# UVB_LED_Controller.net
KiCad netlist of a schematic drawn in Altium Designer
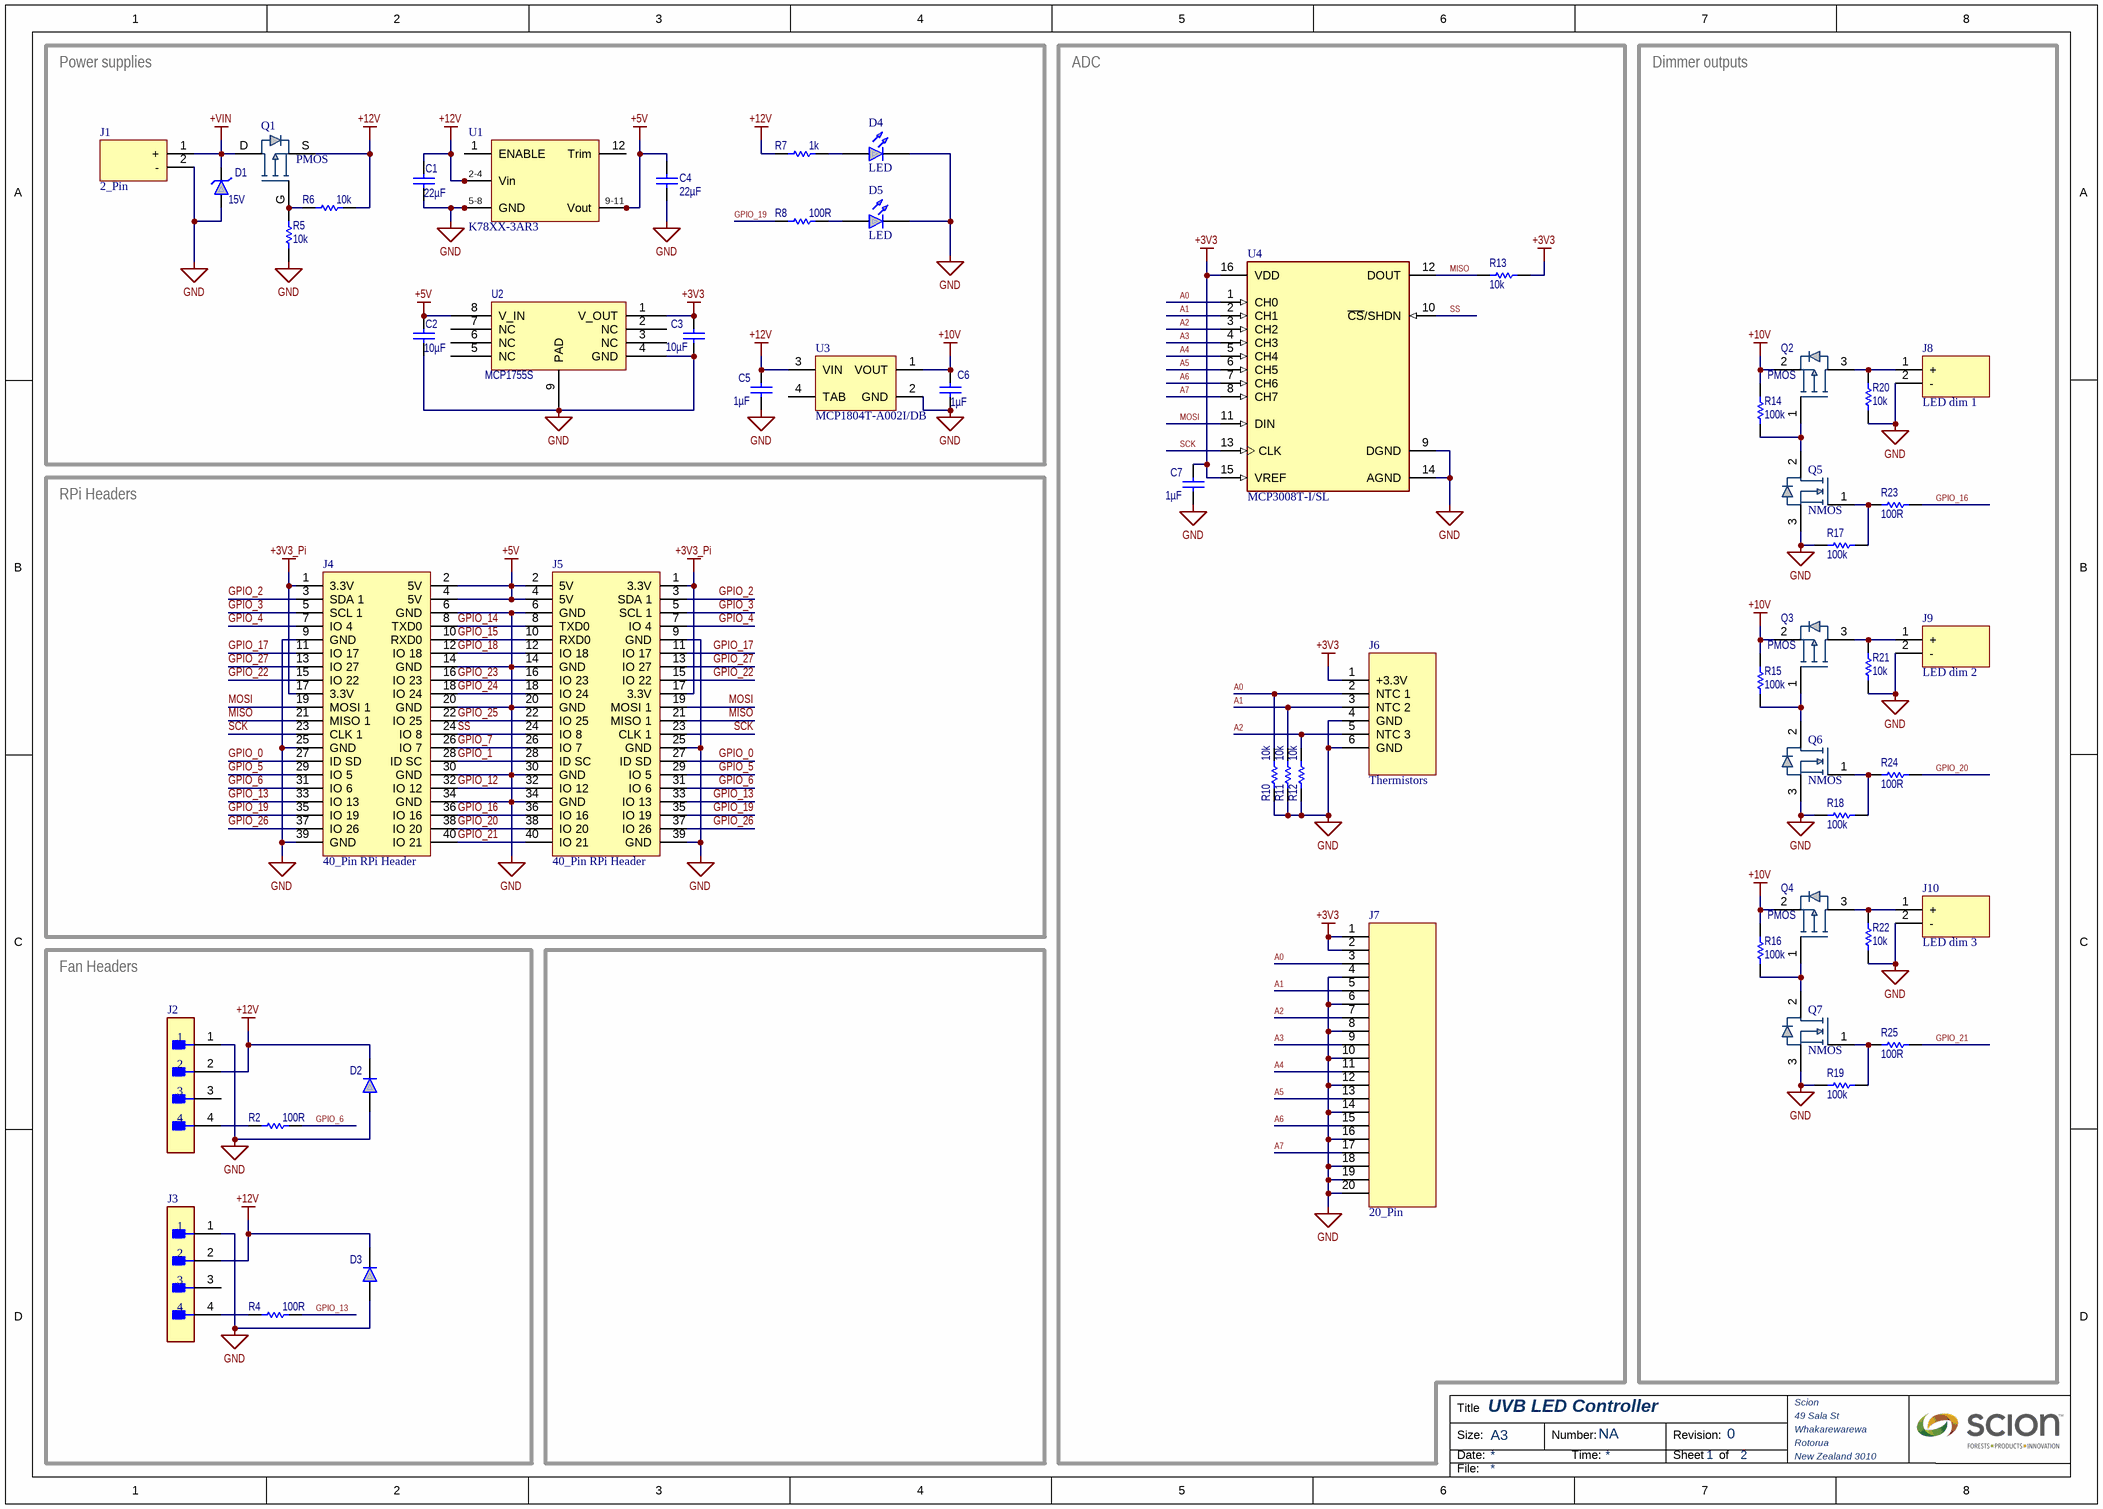
[diagram p0: UVB LED Controller.SchDoc]

(export (version "E")
  (design (tool "Eeschema 10.0.6"))
  (components
    (comp (ref "C1")
      (value "22µF")
      (footprint "1206_CAP")
      (description "SMD Capacitor")
      (fields (field (name "Comment") "Capacitor"))
      (libsource (lib "Scion Research") (part "CMP-019-00005-2"))
    )
    (comp (ref "C2")
      (value "10µF")
      (footprint "0603_CAP")
      (description "SMD Capacitor")
      (fields (field (name "Comment") "Capacitor"))
      (libsource (lib "Scion Research") (part "CMP-019-00005-2"))
    )
    (comp (ref "C3")
      (value "10µF")
      (footprint "0603_CAP")
      (description "SMD Capacitor")
      (fields (field (name "Comment") "Capacitor"))
      (libsource (lib "Scion Research") (part "CMP-019-00005-2"))
    )
    (comp (ref "C4")
      (value "22µF")
      (footprint "1206_CAP")
      (description "SMD Capacitor")
      (fields (field (name "Comment") "Capacitor"))
      (libsource (lib "Scion Research") (part "CMP-019-00005-2"))
    )
    (comp (ref "C5")
      (value "1µF")
      (footprint "0603_CAP")
      (description "SMD Capacitor")
      (fields (field (name "Comment") "Capacitor"))
      (libsource (lib "Scion Research") (part "CMP-019-00005-2"))
    )
    (comp (ref "C6")
      (value "1µF")
      (footprint "0603_CAP")
      (description "SMD Capacitor")
      (fields (field (name "Comment") "Capacitor"))
      (libsource (lib "Scion Research") (part "CMP-019-00005-2"))
    )
    (comp (ref "C7")
      (value "1µF")
      (footprint "0603_CAP")
      (description "SMD Capacitor")
      (fields (field (name "Comment") "Capacitor"))
      (libsource (lib "Scion Research") (part "CMP-019-00005-2"))
    )
    (comp (ref "D1")
      (value "Transil")
      (footprint "SMBJ")
      (description "Transient Voltage Suppressor")
      (fields (field (name "RATED VOLTAGE") "15V"))
      (libsource (lib "Scion Research") (part "CMP-004-0042-1"))
    )
    (comp (ref "D2")
      (value "Diode")
      (footprint "SOD-123")
      (description "SMD Diode")
      (libsource (lib "Scion Research") (part "Diode"))
    )
    (comp (ref "D3")
      (value "Diode")
      (footprint "SOD-123")
      (description "SMD Diode")
      (libsource (lib "Scion Research") (part "Diode"))
    )
    (comp (ref "D4")
      (value "LED")
      (footprint "KPA-2106S_LED")
      (description "SMD LED")
      (libsource (lib "Scion Research") (part "CMP-004-00032-1"))
    )
    (comp (ref "D5")
      (value "LED")
      (footprint "KPA-2106S_LED")
      (description "SMD LED")
      (libsource (lib "Scion Research") (part "CMP-004-00032-1"))
    )
    (comp (ref "J1")
      (value "2_Pin")
      (footprint "2P 3.81mm Header Plugable")
      (description "2 Pin Connector")
      (libsource (lib "") (part "CMP-002-00074-8_1"))
    )
    (comp (ref "J2")
      (value "22-29-2041")
      (footprint "FP-22-29-2041-MFG")
      (description "CONN HEADER VERT 4POS 2.54MM")
      (libsource (lib "Altium Content Vault") (part "299a8cea1bdcbc3624fe62c390fa72c"))
    )
    (comp (ref "J3")
      (value "22-29-2041")
      (footprint "FP-22-29-2041-MFG")
      (description "CONN HEADER VERT 4POS 2.54MM")
      (libsource (lib "Altium Content Vault") (part "299a8cea1bdcbc3624fe62c390fa72c"))
    )
    (comp (ref "J4")
      (value "40_Pin RPi Header")
      (footprint "40_Pin_0.1in_male_header")
      (description "40 pin header for Raspberry Pi compatible connections")
      (libsource (lib "") (part "40_Pin RPi Header_1"))
    )
    (comp (ref "J5")
      (value "40_Pin RPi Header")
      (footprint "40_Pin_0.1in_female_header")
      (description "40 pin header for Raspberry Pi compatible connections")
      (libsource (lib "Scion Research") (part "40_Pin RPi Header"))
    )
    (comp (ref "J6")
      (value "Thermistors")
      (footprint "6P RA MOLEX Clik-MATE 1.5mm")
      (description "6 Pin Connector")
      (libsource (lib "Scion Research") (part "CMP-002-00081-5"))
    )
    (comp (ref "J7")
      (value "20_Pin")
      (footprint "20P 2.54mm DIP header")
      (description "20 pin connector")
      (libsource (lib "Scion Research") (part "20_Pin-Symbol-1"))
    )
    (comp (ref "J8")
      (value "LED dim 1")
      (footprint "2P 3.81mm Header Plugable")
      (description "2 Pin Connector")
      (libsource (lib "Scion Research") (part "CMP-002-00074-8"))
    )
    (comp (ref "J9")
      (value "LED dim 2")
      (footprint "2P 3.81mm Header Plugable")
      (description "2 Pin Connector")
      (libsource (lib "Scion Research") (part "CMP-002-00074-8"))
    )
    (comp (ref "J10")
      (value "LED dim 3")
      (footprint "2P 3.81mm Header Plugable")
      (description "2 Pin Connector")
      (libsource (lib "Scion Research") (part "CMP-002-00074-8"))
    )
    (comp (ref "Q1")
      (value "PMOS")
      (footprint "PowerDI 5060-8")
      (description "P Channel MOSFET")
      (libsource (lib "Scion Research") (part "CMP-004-0035-2"))
    )
    (comp (ref "Q2")
      (value "PMOS")
      (footprint "SOT-23-PMOS")
      (description "P Channel MOSFET")
      (libsource (lib "Scion Research") (part "CMP-004-0033-1"))
    )
    (comp (ref "Q3")
      (value "PMOS")
      (footprint "SOT-23-PMOS")
      (description "P Channel MOSFET")
      (libsource (lib "Scion Research") (part "CMP-004-0033-1"))
    )
    (comp (ref "Q4")
      (value "PMOS")
      (footprint "SOT-23-PMOS")
      (description "P Channel MOSFET")
      (libsource (lib "Scion Research") (part "CMP-004-0033-1"))
    )
    (comp (ref "Q5")
      (value "NMOS")
      (footprint "SOT-23")
      (description "N Channel MOSFET")
      (libsource (lib "Scion Research") (part "CMP-004-0025-1"))
    )
    (comp (ref "Q6")
      (value "NMOS")
      (footprint "SOT-23")
      (description "N Channel MOSFET")
      (libsource (lib "Scion Research") (part "CMP-004-0025-1"))
    )
    (comp (ref "Q7")
      (value "NMOS")
      (footprint "SOT-23")
      (description "N Channel MOSFET")
      (libsource (lib "Scion Research") (part "CMP-004-0025-1"))
    )
    (comp (ref "R2")
      (value "Resistor")
      (footprint "0603_RES")
      (description "SMD Resistor")
      (fields (field (name "ALTIUM_VALUE") "100R"))
      (libsource (lib "Scion Research") (part "CMP-009-00177-2"))
    )
    (comp (ref "R4")
      (value "Resistor")
      (footprint "0603_RES")
      (description "SMD Resistor")
      (fields (field (name "ALTIUM_VALUE") "100R"))
      (libsource (lib "Scion Research") (part "CMP-009-00177-2"))
    )
    (comp (ref "R5")
      (value "Resistor")
      (footprint "0603_RES")
      (description "SMD Resistor")
      (fields (field (name "ALTIUM_VALUE") "10k"))
      (libsource (lib "Scion Research") (part "CMP-009-00177-2"))
    )
    (comp (ref "R6")
      (value "Resistor")
      (footprint "0603_RES")
      (description "SMD Resistor")
      (fields (field (name "ALTIUM_VALUE") "10k"))
      (libsource (lib "Scion Research") (part "CMP-009-00177-2"))
    )
    (comp (ref "R7")
      (value "Resistor")
      (footprint "0603_RES")
      (description "SMD Resistor")
      (fields (field (name "ALTIUM_VALUE") "1k"))
      (libsource (lib "Scion Research") (part "CMP-009-00177-2"))
    )
    (comp (ref "R8")
      (value "Resistor")
      (footprint "0603_RES")
      (description "SMD Resistor")
      (fields (field (name "ALTIUM_VALUE") "100R"))
      (libsource (lib "Scion Research") (part "CMP-009-00177-2"))
    )
    (comp (ref "R10")
      (value "Resistor")
      (footprint "0603_RES")
      (description "SMD Resistor")
      (fields (field (name "ALTIUM_VALUE") "10k"))
      (libsource (lib "Scion Research") (part "CMP-009-00177-2"))
    )
    (comp (ref "R11")
      (value "Resistor")
      (footprint "0603_RES")
      (description "SMD Resistor")
      (fields (field (name "ALTIUM_VALUE") "10k"))
      (libsource (lib "Scion Research") (part "CMP-009-00177-2"))
    )
    (comp (ref "R12")
      (value "Resistor")
      (footprint "0603_RES")
      (description "SMD Resistor")
      (fields (field (name "ALTIUM_VALUE") "10k"))
      (libsource (lib "Scion Research") (part "CMP-009-00177-2"))
    )
    (comp (ref "R13")
      (value "Resistor")
      (footprint "0603_RES")
      (description "SMD Resistor")
      (fields (field (name "ALTIUM_VALUE") "10k"))
      (libsource (lib "Scion Research") (part "CMP-009-00177-2"))
    )
    (comp (ref "R14")
      (value "Resistor")
      (footprint "0603_RES")
      (description "SMD Resistor")
      (fields (field (name "ALTIUM_VALUE") "100k"))
      (libsource (lib "Scion Research") (part "CMP-009-00177-2"))
    )
    (comp (ref "R15")
      (value "Resistor")
      (footprint "0603_RES")
      (description "SMD Resistor")
      (fields (field (name "ALTIUM_VALUE") "100k"))
      (libsource (lib "Scion Research") (part "CMP-009-00177-2"))
    )
    (comp (ref "R16")
      (value "Resistor")
      (footprint "0603_RES")
      (description "SMD Resistor")
      (fields (field (name "ALTIUM_VALUE") "100k"))
      (libsource (lib "Scion Research") (part "CMP-009-00177-2"))
    )
    (comp (ref "R17")
      (value "Resistor")
      (footprint "0603_RES")
      (description "SMD Resistor")
      (fields (field (name "ALTIUM_VALUE") "100k"))
      (libsource (lib "Scion Research") (part "CMP-009-00177-2"))
    )
    (comp (ref "R18")
      (value "Resistor")
      (footprint "0603_RES")
      (description "SMD Resistor")
      (fields (field (name "ALTIUM_VALUE") "100k"))
      (libsource (lib "Scion Research") (part "CMP-009-00177-2"))
    )
    (comp (ref "R19")
      (value "Resistor")
      (footprint "0603_RES")
      (description "SMD Resistor")
      (fields (field (name "ALTIUM_VALUE") "100k"))
      (libsource (lib "Scion Research") (part "CMP-009-00177-2"))
    )
    (comp (ref "R20")
      (value "Resistor")
      (footprint "0603_RES")
      (description "SMD Resistor")
      (fields (field (name "ALTIUM_VALUE") "10k"))
      (libsource (lib "Scion Research") (part "CMP-009-00177-2"))
    )
    (comp (ref "R21")
      (value "Resistor")
      (footprint "0603_RES")
      (description "SMD Resistor")
      (fields (field (name "ALTIUM_VALUE") "10k"))
      (libsource (lib "Scion Research") (part "CMP-009-00177-2"))
    )
    (comp (ref "R22")
      (value "Resistor")
      (footprint "0603_RES")
      (description "SMD Resistor")
      (fields (field (name "ALTIUM_VALUE") "10k"))
      (libsource (lib "Scion Research") (part "CMP-009-00177-2"))
    )
    (comp (ref "R23")
      (value "Resistor")
      (footprint "0603_RES")
      (description "SMD Resistor")
      (fields (field (name "ALTIUM_VALUE") "100R"))
      (libsource (lib "Scion Research") (part "CMP-009-00177-2"))
    )
    (comp (ref "R24")
      (value "Resistor")
      (footprint "0603_RES")
      (description "SMD Resistor")
      (fields (field (name "ALTIUM_VALUE") "100R"))
      (libsource (lib "Scion Research") (part "CMP-009-00177-2"))
    )
    (comp (ref "R25")
      (value "Resistor")
      (footprint "0603_RES")
      (description "SMD Resistor")
      (fields (field (name "ALTIUM_VALUE") "100R"))
      (libsource (lib "Scion Research") (part "CMP-009-00177-2"))
    )
    (comp (ref "U1")
      (value "K78XX-3AR3")
      (footprint "K78XX-3AR3-Footprint")
      (description "Mornsun DC-DC power module 3A, 0-36Vin, 3.3-15V out")
      (libsource (lib "Scion Research") (part "K78XX-3AR3"))
    )
    (comp (ref "U2")
      (value "MCP1755S")
      (footprint "8P 2x3 DFN")
      (description "LDO Linear Voltage Regulator")
      (libsource (lib "Scion Research") (part "CMP-004-0021-1"))
    )
    (comp (ref "U3")
      (value "MCP1804T-A002I/DB")
      (footprint "SOT-223-DB3_N")
      (description "150 mA, 28V LDO Regulator With Shutdown, 3-Pin SOT-223, Industrial Temperature, Tape and Reel")
      (libsource (lib "Altium Content Vault") (part "PM-LINEREG-MCP1804T-SOT4"))
    )
    (comp (ref "U4")
      (value "MCP3008T-I/SL")
      (footprint "FP-C04-108-MFG")
      (description "IC ADC 10BIT SAR 16SOIC")
      (libsource (lib "Altium Content Vault") (part "049cb4bd9558e05d9b89494b6be139f"))
    )
  )
  (nets
    (net (code "1") (name "+3V3") (class "Default")
      (node (ref "C3") (pin "1") (pinfunction "1_1") (pintype "passive"))
      (node (ref "C7") (pin "1") (pinfunction "1_1") (pintype "passive"))
      (node (ref "J6") (pin "1") (pinfunction "+3.3V_1") (pintype "passive"))
      (node (ref "J7") (pin "1") (pinfunction "1_1") (pintype "passive"))
      (node (ref "J7") (pin "2") (pinfunction "2_2") (pintype "passive"))
      (node (ref "R13") (pin "1") (pinfunction "1_1") (pintype "passive"))
      (node (ref "U2") (pin "1") (pinfunction "V_OUT_1") (pintype "power_in"))
      (node (ref "U4") (pin "15") (pinfunction "VREF_15") (pintype "input"))
      (node (ref "U4") (pin "16") (pinfunction "VDD_16") (pintype "power_in"))
    )
    (net (code "2") (name "+3V3_Pi") (class "Default")
      (node (ref "J4") (pin "1") (pinfunction "3.3V_1") (pintype "passive"))
      (node (ref "J4") (pin "17") (pinfunction "3.3V_17") (pintype "passive"))
      (node (ref "J5") (pin "1") (pinfunction "3.3V_1") (pintype "passive"))
      (node (ref "J5") (pin "17") (pinfunction "3.3V_17") (pintype "passive"))
    )
    (net (code "3") (name "+5V") (class "Default")
      (node (ref "C2") (pin "1") (pinfunction "1_1") (pintype "passive"))
      (node (ref "C4") (pin "2") (pinfunction "2_2") (pintype "passive"))
      (node (ref "J4") (pin "2") (pinfunction "5V_2") (pintype "passive"))
      (node (ref "J4") (pin "4") (pinfunction "5V_4") (pintype "passive"))
      (node (ref "J5") (pin "2") (pinfunction "5V_2") (pintype "passive"))
      (node (ref "J5") (pin "4") (pinfunction "5V_4") (pintype "passive"))
      (node (ref "U1") (pin "10") (pinfunction "Vout_10") (pintype "passive"))
      (node (ref "U1") (pin "11") (pinfunction "Vout_11") (pintype "passive"))
      (node (ref "U1") (pin "9") (pinfunction "Vout_9") (pintype "passive"))
      (node (ref "U2") (pin "8") (pinfunction "V_IN_8") (pintype "power_in"))
    )
    (net (code "4") (name "+10V") (class "Default")
      (node (ref "C6") (pin "1") (pinfunction "1_1") (pintype "passive"))
      (node (ref "Q2") (pin "2") (pinfunction "S_2") (pintype "passive"))
      (node (ref "Q3") (pin "2") (pinfunction "S_2") (pintype "passive"))
      (node (ref "Q4") (pin "2") (pinfunction "S_2") (pintype "passive"))
      (node (ref "R14") (pin "2") (pinfunction "2_2") (pintype "passive"))
      (node (ref "R15") (pin "2") (pinfunction "2_2") (pintype "passive"))
      (node (ref "R16") (pin "2") (pinfunction "2_2") (pintype "passive"))
      (node (ref "U3") (pin "1") (pinfunction "VOUT_1") (pintype "power_in"))
    )
    (net (code "5") (name "+12V") (class "Default")
      (node (ref "C1") (pin "1") (pinfunction "1_1") (pintype "passive"))
      (node (ref "C5") (pin "1") (pinfunction "1_1") (pintype "passive"))
      (node (ref "D2") (pin "1") (pinfunction "K_1") (pintype "passive"))
      (node (ref "D3") (pin "1") (pinfunction "K_1") (pintype "passive"))
      (node (ref "J2") (pin "2") (pinfunction "2_2") (pintype "passive"))
      (node (ref "J3") (pin "2") (pinfunction "2_2") (pintype "passive"))
      (node (ref "Q1") (pin "S") (pinfunction "S_S") (pintype "passive"))
      (node (ref "R6") (pin "2") (pinfunction "2_2") (pintype "passive"))
      (node (ref "R7") (pin "1") (pinfunction "1_1") (pintype "passive"))
      (node (ref "U1") (pin "2") (pinfunction "Vin_2") (pintype "passive"))
      (node (ref "U1") (pin "3") (pinfunction "Vin_3") (pintype "passive"))
      (node (ref "U1") (pin "4") (pinfunction "Vin_4") (pintype "passive"))
      (node (ref "U3") (pin "3") (pinfunction "VIN_3") (pintype "power_in"))
    )
    (net (code "6") (name "+VIN") (class "Default")
      (node (ref "D1") (pin "2") (pinfunction "K_2") (pintype "passive"))
      (node (ref "J1") (pin "1") (pinfunction "+_1") (pintype "passive"))
      (node (ref "Q1") (pin "D") (pinfunction "D_D") (pintype "passive"))
    )
    (net (code "7") (name "/A0") (class "Default")
      (node (ref "J6") (pin "2") (pinfunction "NTC_1_2") (pintype "passive"))
      (node (ref "J7") (pin "3") (pinfunction "3_3") (pintype "passive"))
      (node (ref "R10") (pin "2") (pinfunction "2_2") (pintype "passive"))
      (node (ref "U4") (pin "1") (pinfunction "CH0_1") (pintype "input"))
    )
    (net (code "8") (name "/A1") (class "Default")
      (node (ref "J6") (pin "3") (pinfunction "NTC_2_3") (pintype "passive"))
      (node (ref "J7") (pin "5") (pinfunction "5_5") (pintype "passive"))
      (node (ref "R11") (pin "2") (pinfunction "2_2") (pintype "passive"))
      (node (ref "U4") (pin "2") (pinfunction "CH1_2") (pintype "input"))
    )
    (net (code "9") (name "/A2") (class "Default")
      (node (ref "J6") (pin "5") (pinfunction "NTC_3_5") (pintype "passive"))
      (node (ref "J7") (pin "7") (pinfunction "7_7") (pintype "passive"))
      (node (ref "R12") (pin "2") (pinfunction "2_2") (pintype "passive"))
      (node (ref "U4") (pin "3") (pinfunction "CH2_3") (pintype "input"))
    )
    (net (code "10") (name "/A3") (class "Default")
      (node (ref "J7") (pin "9") (pinfunction "9_9") (pintype "passive"))
      (node (ref "U4") (pin "4") (pinfunction "CH3_4") (pintype "input"))
    )
    (net (code "11") (name "/A4") (class "Default")
      (node (ref "J7") (pin "11") (pinfunction "11_11") (pintype "passive"))
      (node (ref "U4") (pin "5") (pinfunction "CH4_5") (pintype "input"))
    )
    (net (code "12") (name "/A5") (class "Default")
      (node (ref "J7") (pin "13") (pinfunction "13_13") (pintype "passive"))
      (node (ref "U4") (pin "6") (pinfunction "CH5_6") (pintype "input"))
    )
    (net (code "13") (name "/A6") (class "Default")
      (node (ref "J7") (pin "15") (pinfunction "15_15") (pintype "passive"))
      (node (ref "U4") (pin "7") (pinfunction "CH6_7") (pintype "input"))
    )
    (net (code "14") (name "/A7") (class "Default")
      (node (ref "J7") (pin "17") (pinfunction "17_17") (pintype "passive"))
      (node (ref "U4") (pin "8") (pinfunction "CH7_8") (pintype "input"))
    )
    (net (code "15") (name "/GPIO_0") (class "Default")
      (node (ref "J4") (pin "27") (pinfunction "ID_SD_27") (pintype "passive"))
      (node (ref "J5") (pin "27") (pinfunction "ID_SD_27") (pintype "passive"))
    )
    (net (code "16") (name "/GPIO_1") (class "Default")
      (node (ref "J4") (pin "28") (pinfunction "ID_SC_28") (pintype "passive"))
      (node (ref "J5") (pin "28") (pinfunction "ID_SC_28") (pintype "passive"))
    )
    (net (code "17") (name "/GPIO_2") (class "Default")
      (node (ref "J4") (pin "3") (pinfunction "SDA_1_3") (pintype "passive"))
      (node (ref "J5") (pin "3") (pinfunction "SDA_1_3") (pintype "passive"))
    )
    (net (code "18") (name "/GPIO_3") (class "Default")
      (node (ref "J4") (pin "5") (pinfunction "SCL_1_5") (pintype "passive"))
      (node (ref "J5") (pin "5") (pinfunction "SCL_1_5") (pintype "passive"))
    )
    (net (code "19") (name "/GPIO_4") (class "Default")
      (node (ref "J4") (pin "7") (pinfunction "IO_4_7") (pintype "passive"))
      (node (ref "J5") (pin "7") (pinfunction "IO_4_7") (pintype "passive"))
    )
    (net (code "20") (name "/GPIO_5") (class "Default")
      (node (ref "J4") (pin "29") (pinfunction "IO_5_29") (pintype "passive"))
      (node (ref "J5") (pin "29") (pinfunction "IO_5_29") (pintype "passive"))
    )
    (net (code "21") (name "/GPIO_6") (class "Default")
      (node (ref "J4") (pin "31") (pinfunction "IO_6_31") (pintype "passive"))
      (node (ref "J5") (pin "31") (pinfunction "IO_6_31") (pintype "passive"))
      (node (ref "R2") (pin "2") (pinfunction "2_2") (pintype "passive"))
    )
    (net (code "22") (name "/GPIO_7") (class "Default")
      (node (ref "J4") (pin "26") (pinfunction "IO_7_26") (pintype "passive"))
      (node (ref "J5") (pin "26") (pinfunction "IO_7_26") (pintype "passive"))
    )
    (net (code "23") (name "/GPIO_12") (class "Default")
      (node (ref "J4") (pin "32") (pinfunction "IO_12_32") (pintype "passive"))
      (node (ref "J5") (pin "32") (pinfunction "IO_12_32") (pintype "passive"))
    )
    (net (code "24") (name "/GPIO_13") (class "Default")
      (node (ref "J4") (pin "33") (pinfunction "IO_13_33") (pintype "passive"))
      (node (ref "J5") (pin "33") (pinfunction "IO_13_33") (pintype "passive"))
      (node (ref "R4") (pin "2") (pinfunction "2_2") (pintype "passive"))
    )
    (net (code "25") (name "/GPIO_14") (class "Default")
      (node (ref "J4") (pin "8") (pinfunction "TXD0_8") (pintype "passive"))
      (node (ref "J5") (pin "8") (pinfunction "TXD0_8") (pintype "passive"))
    )
    (net (code "26") (name "/GPIO_15") (class "Default")
      (node (ref "J4") (pin "10") (pinfunction "RXD0_10") (pintype "passive"))
      (node (ref "J5") (pin "10") (pinfunction "RXD0_10") (pintype "passive"))
    )
    (net (code "27") (name "/GPIO_16") (class "Default")
      (node (ref "J4") (pin "36") (pinfunction "IO_16_36") (pintype "passive"))
      (node (ref "J5") (pin "36") (pinfunction "IO_16_36") (pintype "passive"))
      (node (ref "R23") (pin "1") (pinfunction "1_1") (pintype "passive"))
    )
    (net (code "28") (name "/GPIO_17") (class "Default")
      (node (ref "J4") (pin "11") (pinfunction "IO_17_11") (pintype "passive"))
      (node (ref "J5") (pin "11") (pinfunction "IO_17_11") (pintype "passive"))
    )
    (net (code "29") (name "/GPIO_18") (class "Default")
      (node (ref "J4") (pin "12") (pinfunction "IO_18_12") (pintype "passive"))
      (node (ref "J5") (pin "12") (pinfunction "IO_18_12") (pintype "passive"))
    )
    (net (code "30") (name "/GPIO_19") (class "Default")
      (node (ref "J4") (pin "35") (pinfunction "IO_19_35") (pintype "passive"))
      (node (ref "J5") (pin "35") (pinfunction "IO_19_35") (pintype "passive"))
      (node (ref "R8") (pin "1") (pinfunction "1_1") (pintype "passive"))
    )
    (net (code "31") (name "/GPIO_20") (class "Default")
      (node (ref "J4") (pin "38") (pinfunction "IO_20_38") (pintype "passive"))
      (node (ref "J5") (pin "38") (pinfunction "IO_20_38") (pintype "passive"))
      (node (ref "R24") (pin "1") (pinfunction "1_1") (pintype "passive"))
    )
    (net (code "32") (name "/GPIO_21") (class "Default")
      (node (ref "J4") (pin "40") (pinfunction "IO_21_40") (pintype "passive"))
      (node (ref "J5") (pin "40") (pinfunction "IO_21_40") (pintype "passive"))
      (node (ref "R25") (pin "1") (pinfunction "1_1") (pintype "passive"))
    )
    (net (code "33") (name "/GPIO_22") (class "Default")
      (node (ref "J4") (pin "15") (pinfunction "IO_22_15") (pintype "passive"))
      (node (ref "J5") (pin "15") (pinfunction "IO_22_15") (pintype "passive"))
    )
    (net (code "34") (name "/GPIO_23") (class "Default")
      (node (ref "J4") (pin "16") (pinfunction "IO_23_16") (pintype "passive"))
      (node (ref "J5") (pin "16") (pinfunction "IO_23_16") (pintype "passive"))
    )
    (net (code "35") (name "/GPIO_24") (class "Default")
      (node (ref "J4") (pin "18") (pinfunction "IO_24_18") (pintype "passive"))
      (node (ref "J5") (pin "18") (pinfunction "IO_24_18") (pintype "passive"))
    )
    (net (code "36") (name "/GPIO_25") (class "Default")
      (node (ref "J4") (pin "22") (pinfunction "IO_25_22") (pintype "passive"))
      (node (ref "J5") (pin "22") (pinfunction "IO_25_22") (pintype "passive"))
    )
    (net (code "37") (name "/GPIO_26") (class "Default")
      (node (ref "J4") (pin "37") (pinfunction "IO_26_37") (pintype "passive"))
      (node (ref "J5") (pin "37") (pinfunction "IO_26_37") (pintype "passive"))
    )
    (net (code "38") (name "/GPIO_27") (class "Default")
      (node (ref "J4") (pin "13") (pinfunction "IO_27_13") (pintype "passive"))
      (node (ref "J5") (pin "13") (pinfunction "IO_27_13") (pintype "passive"))
    )
    (net (code "39") (name "/MISO") (class "Default")
      (node (ref "J4") (pin "21") (pinfunction "MISO_1_21") (pintype "passive"))
      (node (ref "J5") (pin "21") (pinfunction "MISO_1_21") (pintype "passive"))
      (node (ref "R13") (pin "2") (pinfunction "2_2") (pintype "passive"))
      (node (ref "U4") (pin "12") (pinfunction "DOUT_12") (pintype "tri_state"))
    )
    (net (code "40") (name "/MOSI") (class "Default")
      (node (ref "J4") (pin "19") (pinfunction "MOSI_1_19") (pintype "passive"))
      (node (ref "J5") (pin "19") (pinfunction "MOSI_1_19") (pintype "passive"))
      (node (ref "U4") (pin "11") (pinfunction "DIN_11") (pintype "input"))
    )
    (net (code "41") (name "/SCK") (class "Default")
      (node (ref "J4") (pin "23") (pinfunction "CLK_1_23") (pintype "passive"))
      (node (ref "J5") (pin "23") (pinfunction "CLK_1_23") (pintype "passive"))
      (node (ref "U4") (pin "13") (pinfunction "CLK_13") (pintype "input"))
    )
    (net (code "42") (name "/SS") (class "Default")
      (node (ref "J4") (pin "24") (pinfunction "IO_8_24") (pintype "passive"))
      (node (ref "J5") (pin "24") (pinfunction "IO_8_24") (pintype "passive"))
      (node (ref "U4") (pin "10") (pinfunction "~{CS}/SHDN_10") (pintype "input"))
    )
    (net (code "43") (name "GND") (class "Default")
      (node (ref "C1") (pin "2") (pinfunction "2_2") (pintype "passive"))
      (node (ref "C2") (pin "2") (pinfunction "2_2") (pintype "passive"))
      (node (ref "C3") (pin "2") (pinfunction "2_2") (pintype "passive"))
      (node (ref "C4") (pin "1") (pinfunction "1_1") (pintype "passive"))
      (node (ref "C5") (pin "2") (pinfunction "2_2") (pintype "passive"))
      (node (ref "C6") (pin "2") (pinfunction "2_2") (pintype "passive"))
      (node (ref "C7") (pin "2") (pinfunction "2_2") (pintype "passive"))
      (node (ref "D1") (pin "1") (pinfunction "A_1") (pintype "passive"))
      (node (ref "D2") (pin "2") (pinfunction "A_2") (pintype "passive"))
      (node (ref "D3") (pin "2") (pinfunction "A_2") (pintype "passive"))
      (node (ref "D4") (pin "1") (pinfunction "K_1") (pintype "passive"))
      (node (ref "D5") (pin "1") (pinfunction "K_1") (pintype "passive"))
      (node (ref "J1") (pin "2") (pinfunction "-_2") (pintype "passive"))
      (node (ref "J10") (pin "2") (pinfunction "-_2") (pintype "passive"))
      (node (ref "J2") (pin "1") (pinfunction "1_1") (pintype "passive"))
      (node (ref "J3") (pin "1") (pinfunction "1_1") (pintype "passive"))
      (node (ref "J4") (pin "14") (pinfunction "GND_14") (pintype "passive"))
      (node (ref "J4") (pin "20") (pinfunction "GND_20") (pintype "passive"))
      (node (ref "J4") (pin "25") (pinfunction "GND_25") (pintype "passive"))
      (node (ref "J4") (pin "30") (pinfunction "GND_30") (pintype "passive"))
      (node (ref "J4") (pin "34") (pinfunction "GND_34") (pintype "passive"))
      (node (ref "J4") (pin "39") (pinfunction "GND_39") (pintype "passive"))
      (node (ref "J4") (pin "6") (pinfunction "GND_6") (pintype "passive"))
      (node (ref "J4") (pin "9") (pinfunction "GND_9") (pintype "passive"))
      (node (ref "J5") (pin "14") (pinfunction "GND_14") (pintype "passive"))
      (node (ref "J5") (pin "20") (pinfunction "GND_20") (pintype "passive"))
      (node (ref "J5") (pin "25") (pinfunction "GND_25") (pintype "passive"))
      (node (ref "J5") (pin "30") (pinfunction "GND_30") (pintype "passive"))
      (node (ref "J5") (pin "34") (pinfunction "GND_34") (pintype "passive"))
      (node (ref "J5") (pin "39") (pinfunction "GND_39") (pintype "passive"))
      (node (ref "J5") (pin "6") (pinfunction "GND_6") (pintype "passive"))
      (node (ref "J5") (pin "9") (pinfunction "GND_9") (pintype "passive"))
      (node (ref "J6") (pin "4") (pinfunction "GND_4") (pintype "passive"))
      (node (ref "J6") (pin "6") (pinfunction "GND_6") (pintype "passive"))
      (node (ref "J7") (pin "10") (pinfunction "10_10") (pintype "passive"))
      (node (ref "J7") (pin "12") (pinfunction "12_12") (pintype "passive"))
      (node (ref "J7") (pin "14") (pinfunction "14_14") (pintype "passive"))
      (node (ref "J7") (pin "16") (pinfunction "16_16") (pintype "passive"))
      (node (ref "J7") (pin "18") (pinfunction "18_18") (pintype "passive"))
      (node (ref "J7") (pin "19") (pinfunction "19_19") (pintype "passive"))
      (node (ref "J7") (pin "20") (pinfunction "20_20") (pintype "passive"))
      (node (ref "J7") (pin "4") (pinfunction "4_4") (pintype "passive"))
      (node (ref "J7") (pin "6") (pinfunction "6_6") (pintype "passive"))
      (node (ref "J7") (pin "8") (pinfunction "8_8") (pintype "passive"))
      (node (ref "J8") (pin "2") (pinfunction "-_2") (pintype "passive"))
      (node (ref "J9") (pin "2") (pinfunction "-_2") (pintype "passive"))
      (node (ref "Q5") (pin "3") (pinfunction "S_3") (pintype "passive"))
      (node (ref "Q6") (pin "3") (pinfunction "S_3") (pintype "passive"))
      (node (ref "Q7") (pin "3") (pinfunction "S_3") (pintype "passive"))
      (node (ref "R10") (pin "1") (pinfunction "1_1") (pintype "passive"))
      (node (ref "R11") (pin "1") (pinfunction "1_1") (pintype "passive"))
      (node (ref "R12") (pin "1") (pinfunction "1_1") (pintype "passive"))
      (node (ref "R17") (pin "2") (pinfunction "2_2") (pintype "passive"))
      (node (ref "R18") (pin "2") (pinfunction "2_2") (pintype "passive"))
      (node (ref "R19") (pin "2") (pinfunction "2_2") (pintype "passive"))
      (node (ref "R20") (pin "1") (pinfunction "1_1") (pintype "passive"))
      (node (ref "R21") (pin "1") (pinfunction "1_1") (pintype "passive"))
      (node (ref "R22") (pin "1") (pinfunction "1_1") (pintype "passive"))
      (node (ref "R5") (pin "1") (pinfunction "1_1") (pintype "passive"))
      (node (ref "U1") (pin "5") (pinfunction "GND_5") (pintype "passive"))
      (node (ref "U1") (pin "6") (pinfunction "GND_6") (pintype "passive"))
      (node (ref "U1") (pin "7") (pinfunction "GND_7") (pintype "passive"))
      (node (ref "U1") (pin "8") (pinfunction "GND_8") (pintype "passive"))
      (node (ref "U2") (pin "4") (pinfunction "GND_4") (pintype "power_in"))
      (node (ref "U2") (pin "9") (pinfunction "PAD_9") (pintype "power_in"))
      (node (ref "U3") (pin "2") (pinfunction "GND_2") (pintype "power_in"))
      (node (ref "U4") (pin "14") (pinfunction "AGND_14") (pintype "power_in"))
      (node (ref "U4") (pin "9") (pinfunction "DGND_9") (pintype "power_in"))
    )
    (net (code "44") (name "Net-(D4-A)") (class "Default")
      (node (ref "D4") (pin "2") (pinfunction "A_2") (pintype "passive"))
      (node (ref "R7") (pin "2") (pinfunction "2_2") (pintype "passive"))
    )
    (net (code "45") (name "Net-(D5-A)") (class "Default")
      (node (ref "D5") (pin "2") (pinfunction "A_2") (pintype "passive"))
      (node (ref "R8") (pin "2") (pinfunction "2_2") (pintype "passive"))
    )
    (net (code "46") (name "Net-(J2-Pad4)") (class "Default")
      (node (ref "J2") (pin "4") (pinfunction "4_4") (pintype "passive"))
      (node (ref "R2") (pin "1") (pinfunction "1_1") (pintype "passive"))
    )
    (net (code "47") (name "Net-(J3-Pad4)") (class "Default")
      (node (ref "J3") (pin "4") (pinfunction "4_4") (pintype "passive"))
      (node (ref "R4") (pin "1") (pinfunction "1_1") (pintype "passive"))
    )
    (net (code "48") (name "Net-(J8-+)") (class "Default")
      (node (ref "J8") (pin "1") (pinfunction "+_1") (pintype "passive"))
      (node (ref "Q2") (pin "3") (pinfunction "D_3") (pintype "passive"))
      (node (ref "R20") (pin "2") (pinfunction "2_2") (pintype "passive"))
    )
    (net (code "49") (name "Net-(J9-+)") (class "Default")
      (node (ref "J9") (pin "1") (pinfunction "+_1") (pintype "passive"))
      (node (ref "Q3") (pin "3") (pinfunction "D_3") (pintype "passive"))
      (node (ref "R21") (pin "2") (pinfunction "2_2") (pintype "passive"))
    )
    (net (code "50") (name "Net-(J10-+)") (class "Default")
      (node (ref "J10") (pin "1") (pinfunction "+_1") (pintype "passive"))
      (node (ref "Q4") (pin "3") (pinfunction "D_3") (pintype "passive"))
      (node (ref "R22") (pin "2") (pinfunction "2_2") (pintype "passive"))
    )
    (net (code "51") (name "Net-(Q1-PadG)") (class "Default")
      (node (ref "Q1") (pin "G") (pinfunction "G_G") (pintype "passive"))
      (node (ref "R5") (pin "2") (pinfunction "2_2") (pintype "passive"))
      (node (ref "R6") (pin "1") (pinfunction "1_1") (pintype "passive"))
    )
    (net (code "52") (name "Net-(Q2-G)") (class "Default")
      (node (ref "Q2") (pin "1") (pinfunction "G_1") (pintype "passive"))
      (node (ref "Q5") (pin "2") (pinfunction "D_2") (pintype "passive"))
      (node (ref "R14") (pin "1") (pinfunction "1_1") (pintype "passive"))
    )
    (net (code "53") (name "Net-(Q3-G)") (class "Default")
      (node (ref "Q3") (pin "1") (pinfunction "G_1") (pintype "passive"))
      (node (ref "Q6") (pin "2") (pinfunction "D_2") (pintype "passive"))
      (node (ref "R15") (pin "1") (pinfunction "1_1") (pintype "passive"))
    )
    (net (code "54") (name "Net-(Q4-G)") (class "Default")
      (node (ref "Q4") (pin "1") (pinfunction "G_1") (pintype "passive"))
      (node (ref "Q7") (pin "2") (pinfunction "D_2") (pintype "passive"))
      (node (ref "R16") (pin "1") (pinfunction "1_1") (pintype "passive"))
    )
    (net (code "55") (name "Net-(Q5-G)") (class "Default")
      (node (ref "Q5") (pin "1") (pinfunction "G_1") (pintype "passive"))
      (node (ref "R17") (pin "1") (pinfunction "1_1") (pintype "passive"))
      (node (ref "R23") (pin "2") (pinfunction "2_2") (pintype "passive"))
    )
    (net (code "56") (name "Net-(Q6-G)") (class "Default")
      (node (ref "Q6") (pin "1") (pinfunction "G_1") (pintype "passive"))
      (node (ref "R18") (pin "1") (pinfunction "1_1") (pintype "passive"))
      (node (ref "R24") (pin "2") (pinfunction "2_2") (pintype "passive"))
    )
    (net (code "57") (name "Net-(Q7-G)") (class "Default")
      (node (ref "Q7") (pin "1") (pinfunction "G_1") (pintype "passive"))
      (node (ref "R19") (pin "1") (pinfunction "1_1") (pintype "passive"))
      (node (ref "R25") (pin "2") (pinfunction "2_2") (pintype "passive"))
    )
    (net (code "58") (name "unconnected-(J2-Pad3)") (class "Default")
      (node (ref "J2") (pin "3") (pinfunction "3_3") (pintype "passive"))
    )
    (net (code "59") (name "unconnected-(J3-Pad3)") (class "Default")
      (node (ref "J3") (pin "3") (pinfunction "3_3") (pintype "passive"))
    )
    (net (code "60") (name "unconnected-(U1-ENABLE-Pad1)") (class "Default")
      (node (ref "U1") (pin "1") (pinfunction "ENABLE_1") (pintype "passive"))
    )
    (net (code "61") (name "unconnected-(U1-Trim-Pad12)") (class "Default")
      (node (ref "U1") (pin "12") (pinfunction "Trim_12") (pintype "passive"))
    )
    (net (code "62") (name "unconnected-(U2-NC-Pad2)") (class "Default")
      (node (ref "U2") (pin "2") (pinfunction "NC_2") (pintype "passive"))
    )
    (net (code "63") (name "unconnected-(U2-NC-Pad3)") (class "Default")
      (node (ref "U2") (pin "3") (pinfunction "NC_3") (pintype "passive"))
    )
    (net (code "64") (name "unconnected-(U2-NC-Pad5)") (class "Default")
      (node (ref "U2") (pin "5") (pinfunction "NC_5") (pintype "passive"))
    )
    (net (code "65") (name "unconnected-(U2-NC-Pad6)") (class "Default")
      (node (ref "U2") (pin "6") (pinfunction "NC_6") (pintype "passive"))
    )
    (net (code "66") (name "unconnected-(U2-NC-Pad7)") (class "Default")
      (node (ref "U2") (pin "7") (pinfunction "NC_7") (pintype "passive"))
    )
    (net (code "67") (name "unconnected-(U3-TAB-Pad4)") (class "Default")
      (node (ref "U3") (pin "4") (pinfunction "TAB_4") (pintype "power_in"))
    )
  )
)
